# LPS22HBTR.net
KiCad netlist of a schematic drawn in Altium Designer
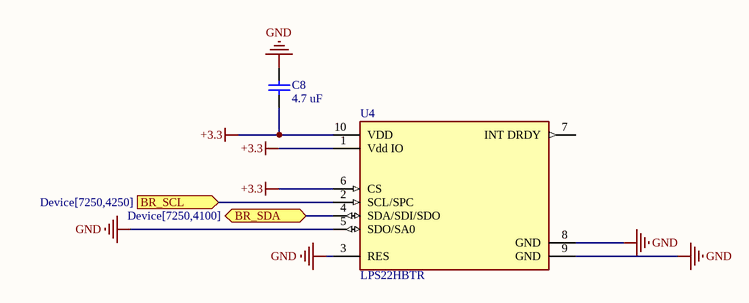
[diagram p0: LPS22HBTR.SchDoc]

(export (version "E")
  (design (tool "Eeschema 10.0.6"))
  (components
    (comp (ref "C8")
      (value "4.7 uF")
      (footprint "CAPC1005X55X25NL05T10")
      (fields (field (name "MANUFACTURER") "Murata") (field (name "PART NUMBER") "GRM155F50J684ZE01D"))
      (libsource (lib "Altium Content Vault") (part "CAP"))
    )
    (comp (ref "U4")
      (value "LPS22HBTR")
      (footprint "FP-HLGA-10L-8479831-0")
      (description "MEMS NANO PRESSURE SENSOR: 260-1")
      (fields
        (field (name "OCTOPART") "https://octopart.com/lps22hbtr-stmicroelectronics-51851131")
        (field (name "MANUFACTURER") "STMicroelectronics")
      )
      (libsource (lib "Altium Content Vault") (part "d4c28707ea3ba579869663dd93796c5"))
    )
  )
  (nets
    (net (code "1") (name "+3.3") (class "Default")
      (node (ref "C8") (pin "2") (pinfunction "2_2") (pintype "passive"))
      (node (ref "U4") (pin "1") (pinfunction "Vdd_IO_1") (pintype "power_in"))
      (node (ref "U4") (pin "10") (pinfunction "VDD_10") (pintype "power_in"))
      (node (ref "U4") (pin "6") (pinfunction "CS_6") (pintype "input"))
    )
    (net (code "2") (name "/BR_SCL") (class "Default")
      (node (ref "U4") (pin "2") (pinfunction "SCL/SPC_2") (pintype "input"))
    )
    (net (code "3") (name "/BR_SDA") (class "Default")
      (node (ref "U4") (pin "4") (pinfunction "SDA/SDI/SDO_4") (pintype "bidirectional"))
    )
    (net (code "4") (name "GND") (class "Default")
      (node (ref "C8") (pin "1") (pinfunction "1_1") (pintype "passive"))
      (node (ref "U4") (pin "3") (pinfunction "RES_3") (pintype "passive"))
      (node (ref "U4") (pin "5") (pinfunction "SDO/SA0_5") (pintype "bidirectional"))
      (node (ref "U4") (pin "8") (pinfunction "GND_8") (pintype "power_in"))
      (node (ref "U4") (pin "9") (pinfunction "GND_9") (pintype "power_in"))
    )
    (net (code "5") (name "unconnected-(U4-INT_DRDY-Pad7)") (class "Default")
      (node (ref "U4") (pin "7") (pinfunction "INT_DRDY_7") (pintype "output"))
    )
  )
)
